# power_supply.net
KiCad netlist of a schematic drawn in Altium Designer
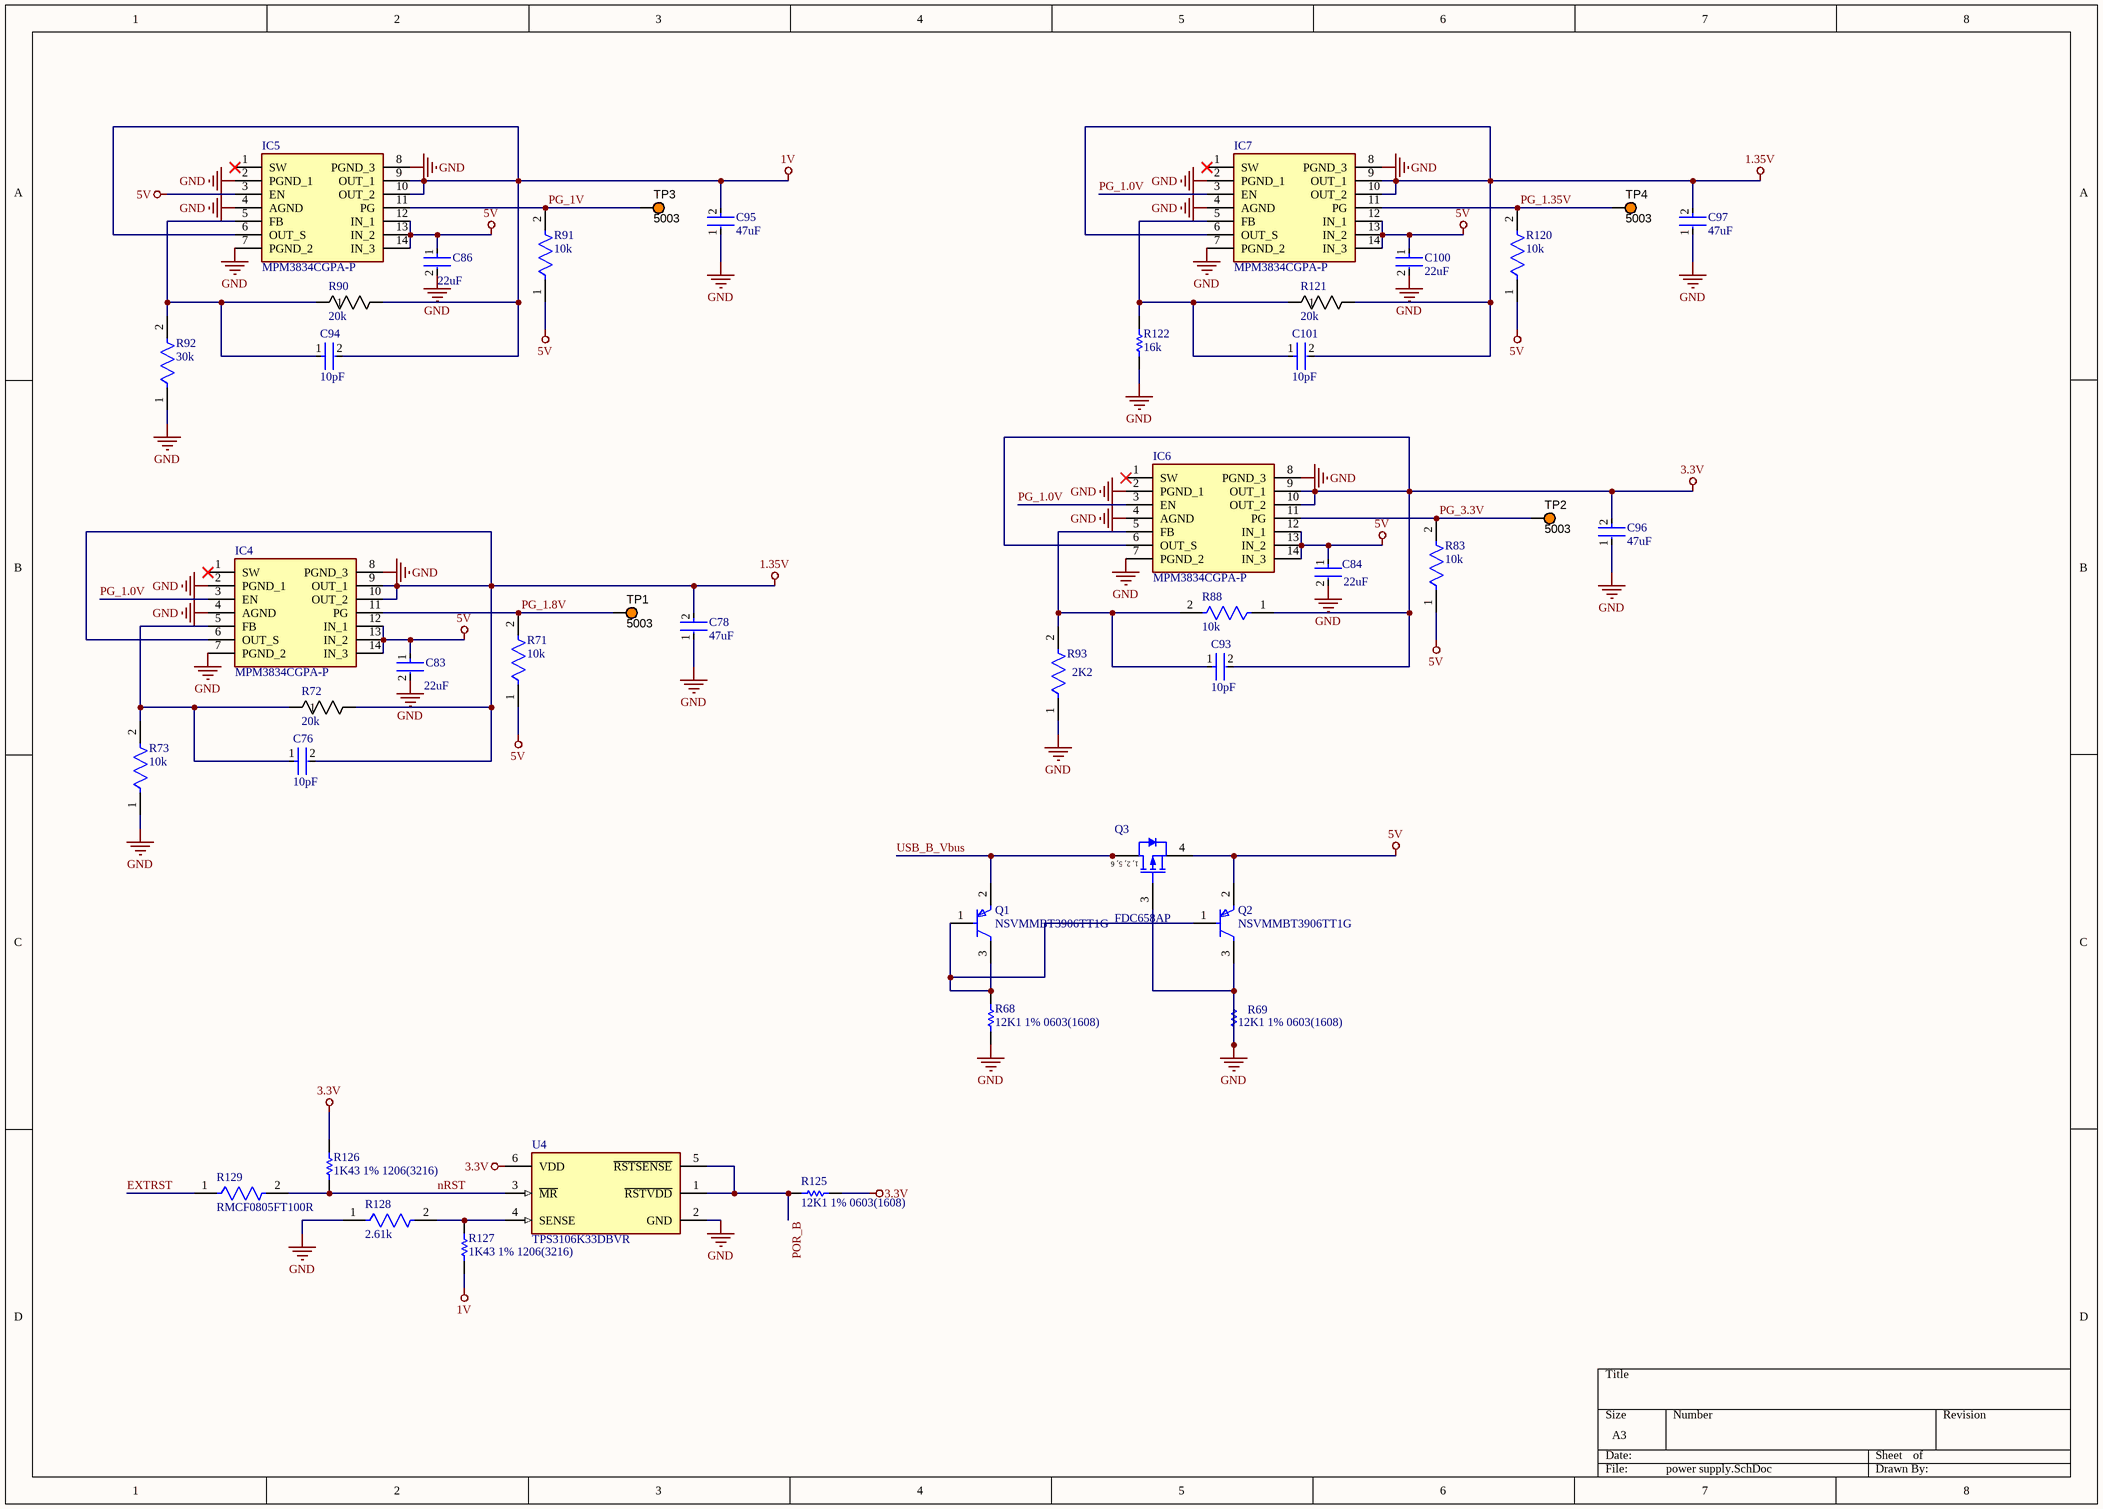
[diagram p0: power supply.SchDoc]

(export (version "E")
  (design (tool "Eeschema 10.0.6"))
  (components
    (comp (ref "C76")
      (value "10pF")
      (footprint "FP-0603-L_1_6_0_15-W_0_81-IPC_B")
      (description "General Purpose Ceramic Capacitor, 0603, 10pF, 2%, NP0, 30ppm/°C, 100V")
      (fields (field (name "TOLERANCE") "2%"))
      (libsource (lib "Altium Content Vault") (part "02cd4be3c70576c341d710602a673aa"))
    )
    (comp (ref "C78")
      (value "47uF")
      (footprint "FP-GRM31C-0_3-e0_3_0_8-IPC_C")
      (description "Chip Multilayer Ceramic Capacitors for General Purpose, 1206, 47uF, X5R, 15%, 20%, 16V")
      (fields (field (name "TOLERANCE") "20%"))
      (libsource (lib "Altium Content Vault") (part "f23184f103b6ebe33a8c269c53dcba6"))
    )
    (comp (ref "C83")
      (value "22uF")
      (footprint "FP-GRMJN7-0_1-IPC_C")
      (description "Chip Multilayer Ceramic Capacitors for General Purpose, 0704, 22uF, X5R, 15%, 20%, 16V")
      (libsource (lib "Altium Content Vault") (part "02cd4be3c70576c341d710602a673aa"))
    )
    (comp (ref "C84")
      (value "22uF")
      (footprint "FP-GRMJN7-0_1-IPC_C")
      (description "Chip Multilayer Ceramic Capacitors for General Purpose, 0704, 22uF, X5R, 15%, 20%, 16V")
      (libsource (lib "Altium Content Vault") (part "02cd4be3c70576c341d710602a673aa"))
    )
    (comp (ref "C86")
      (value "22uF")
      (footprint "FP-GRMJN7-0_1-IPC_C")
      (description "Chip Multilayer Ceramic Capacitors for General Purpose, 0704, 22uF, X5R, 15%, 20%, 16V")
      (libsource (lib "Altium Content Vault") (part "02cd4be3c70576c341d710602a673aa"))
    )
    (comp (ref "C93")
      (value "10pF")
      (footprint "FP-0603-L_1_6_0_15-W_0_81-IPC_B")
      (description "General Purpose Ceramic Capacitor, 0603, 10pF, 2%, NP0, 30ppm/°C, 100V")
      (fields (field (name "TOLERANCE") "2%"))
      (libsource (lib "Altium Content Vault") (part "02cd4be3c70576c341d710602a673aa"))
    )
    (comp (ref "C94")
      (value "10pF")
      (footprint "FP-0603-L_1_6_0_15-W_0_81-IPC_B")
      (description "General Purpose Ceramic Capacitor, 0603, 10pF, 2%, NP0, 30ppm/°C, 100V")
      (fields (field (name "TOLERANCE") "2%"))
      (libsource (lib "Altium Content Vault") (part "02cd4be3c70576c341d710602a673aa"))
    )
    (comp (ref "C95")
      (value "47uF")
      (footprint "FP-GRM31C-0_3-e0_3_0_8-IPC_C")
      (description "Chip Multilayer Ceramic Capacitors for General Purpose, 1206, 47uF, X5R, 15%, 20%, 16V")
      (fields (field (name "TOLERANCE") "20%"))
      (libsource (lib "Altium Content Vault") (part "f23184f103b6ebe33a8c269c53dcba6"))
    )
    (comp (ref "C96")
      (value "47uF")
      (footprint "FP-GRM31C-0_3-e0_3_0_8-IPC_C")
      (description "Chip Multilayer Ceramic Capacitors for General Purpose, 1206, 47uF, X5R, 15%, 20%, 16V")
      (fields (field (name "TOLERANCE") "20%"))
      (libsource (lib "Altium Content Vault") (part "f23184f103b6ebe33a8c269c53dcba6"))
    )
    (comp (ref "C97")
      (value "47uF")
      (footprint "FP-GRM31C-0_3-e0_3_0_8-IPC_C")
      (description "Chip Multilayer Ceramic Capacitors for General Purpose, 1206, 47uF, X5R, 15%, 20%, 16V")
      (fields (field (name "TOLERANCE") "20%"))
      (libsource (lib "Altium Content Vault") (part "f23184f103b6ebe33a8c269c53dcba6"))
    )
    (comp (ref "C100")
      (value "22uF")
      (footprint "FP-GRMJN7-0_1-IPC_C")
      (description "Chip Multilayer Ceramic Capacitors for General Purpose, 0704, 22uF, X5R, 15%, 20%, 16V")
      (libsource (lib "Altium Content Vault") (part "02cd4be3c70576c341d710602a673aa"))
    )
    (comp (ref "C101")
      (value "10pF")
      (footprint "FP-0603-L_1_6_0_15-W_0_81-IPC_B")
      (description "General Purpose Ceramic Capacitor, 0603, 10pF, 2%, NP0, 30ppm/°C, 100V")
      (fields (field (name "TOLERANCE") "2%"))
      (libsource (lib "Altium Content Vault") (part "02cd4be3c70576c341d710602a673aa"))
    )
    (comp (ref "IC4")
      (value "MPM3834CGPA-P")
      (footprint "SamacSys:MPM3834CGPAP")
      (description "Integrated Circuit")
      (fields (field (name "MOUSER PART NUMBER") "946-MPM3834CGPA-P"))
      (libsource (lib "*") (part "MPM3834CGPA-P"))
    )
    (comp (ref "IC5")
      (value "MPM3834CGPA-P")
      (footprint "SamacSys:MPM3834CGPAP")
      (description "Integrated Circuit")
      (fields (field (name "MOUSER PART NUMBER") "946-MPM3834CGPA-P"))
      (libsource (lib "*") (part "MPM3834CGPA-P"))
    )
    (comp (ref "IC6")
      (value "MPM3834CGPA-P")
      (footprint "SamacSys:MPM3834CGPAP")
      (description "Integrated Circuit")
      (fields (field (name "MOUSER PART NUMBER") "946-MPM3834CGPA-P"))
      (libsource (lib "*") (part "MPM3834CGPA-P"))
    )
    (comp (ref "IC7")
      (value "MPM3834CGPA-P")
      (footprint "SamacSys:MPM3834CGPAP")
      (description "Integrated Circuit")
      (fields (field (name "MOUSER PART NUMBER") "946-MPM3834CGPA-P"))
      (libsource (lib "*") (part "MPM3834CGPA-P"))
    )
    (comp (ref "Q1")
      (value "NSVMMBT3906TT1G")
      (footprint "FP-463-01-MFG")
      (description "NSVMMBT3906TT1G Small Signal Bipolar Transistor, 0.2A I(C), 40V V(BR)CEO, 1-Element, PNP, Silicon")
      (libsource (lib "Altium Content Vault") (part "ffd30bc5d0a750d7d7ef0ebafdf4ab0"))
    )
    (comp (ref "Q2")
      (value "NSVMMBT3906TT1G")
      (footprint "FP-463-01-MFG")
      (description "NSVMMBT3906TT1G Small Signal Bipolar Transistor, 0.2A I(C), 40V V(BR)CEO, 1-Element, PNP, Silicon")
      (libsource (lib "Altium Content Vault") (part "ffd30bc5d0a750d7d7ef0ebafdf4ab0"))
    )
    (comp (ref "Q3")
      (value "FDC658AP")
      (footprint "FAIR-SOT23-6_V")
      (fields (field (name "MANUFACTURER") "Fairchild Semiconductor"))
      (libsource (lib "Altium Content Vault") (part "PEMOS-DDGSDD-6"))
    )
    (comp (ref "R68")
      (value "12K1 1% 0603(1608)")
      (footprint "RESC0603(1608)_M")
      (description "12K1 0.1W 1% 0603 (1608 Metric)  SMD")
      (fields (field (name "POWER") "0.1 W") (field (name "TOLERANCE") "1 %"))
      (libsource (lib "Altium Content Vault") (part "RES"))
    )
    (comp (ref "R69")
      (value "12K1 1% 0603(1608)")
      (footprint "RESC0603(1608)_M")
      (description "12K1 0.1W 1% 0603 (1608 Metric)  SMD")
      (fields (field (name "POWER") "0.1 W") (field (name "TOLERANCE") "1 %"))
      (libsource (lib "Altium Content Vault") (part "RES"))
    )
    (comp (ref "R71")
      (value "10k")
      (footprint "FP-RN73R2A-IPC_A")
      (description "RES 10K OHM 0.1% 1/8W 0805")
      (libsource (lib "Altium Content Vault") (part "1029c3af85768c4190bb7ad29bc67b5"))
    )
    (comp (ref "R72")
      (value "20k")
      (footprint "RES_RCC0402_VIS")
      (description "RCC040220K0FKED Res Thick Film 0402 20K Ohm 1% 0.125W(1/8W) ±100ppm/°C Pad SMD Automotive T/R")
      (libsource (lib "Altium Content Vault") (part "RCC040220K0FKED"))
    )
    (comp (ref "R73")
      (value "10k")
      (footprint "FP-RN73R2A-IPC_A")
      (description "RES 10K OHM 0.1% 1/8W 0805")
      (libsource (lib "Altium Content Vault") (part "1029c3af85768c4190bb7ad29bc67b5"))
    )
    (comp (ref "R83")
      (value "10k")
      (footprint "FP-RN73R2A-IPC_A")
      (description "RES 10K OHM 0.1% 1/8W 0805")
      (libsource (lib "Altium Content Vault") (part "1029c3af85768c4190bb7ad29bc67b5"))
    )
    (comp (ref "R88")
      (value "10k")
      (footprint "FP-RN73R2A-IPC_A")
      (description "RES 10K OHM 0.1% 1/8W 0805")
      (libsource (lib "Altium Content Vault") (part "1029c3af85768c4190bb7ad29bc67b5"))
    )
    (comp (ref "R90")
      (value "20k")
      (footprint "RES_RCC0402_VIS")
      (description "RCC040220K0FKED Res Thick Film 0402 20K Ohm 1% 0.125W(1/8W) ±100ppm/°C Pad SMD Automotive T/R")
      (libsource (lib "Altium Content Vault") (part "RCC040220K0FKED"))
    )
    (comp (ref "R91")
      (value "10k")
      (footprint "FP-RN73R2A-IPC_A")
      (description "RES 10K OHM 0.1% 1/8W 0805")
      (libsource (lib "Altium Content Vault") (part "1029c3af85768c4190bb7ad29bc67b5"))
    )
    (comp (ref "R92")
      (value "30k")
      (footprint "FP-RMCF0603-IPC_A")
      (description "30kΩ ±5% 0.1W 0603 Thick Film Chip Resistor AEC-Q200 compliant")
      (fields (field (name "TOLERANCE") "5%"))
      (libsource (lib "Altium Content Vault") (part "1029c3af85768c4190bb7ad29bc67b5"))
    )
    (comp (ref "R93")
      (value "2K2")
      (footprint "FP-LTR10-IPC_B")
      (description "High power chip resistors wide terminal type 2.2kΩ 5% 0.25W 0508")
      (fields (field (name "TOLERANCE") "5%"))
      (libsource (lib "Altium Content Vault") (part "1029c3af85768c4190bb7ad29bc67b5"))
    )
    (comp (ref "R120")
      (value "10k")
      (footprint "FP-RN73R2A-IPC_A")
      (description "RES 10K OHM 0.1% 1/8W 0805")
      (libsource (lib "Altium Content Vault") (part "1029c3af85768c4190bb7ad29bc67b5"))
    )
    (comp (ref "R121")
      (value "20k")
      (footprint "RES_RCC0402_VIS")
      (description "RCC040220K0FKED Res Thick Film 0402 20K Ohm 1% 0.125W(1/8W) ±100ppm/°C Pad SMD Automotive T/R")
      (libsource (lib "Altium Content Vault") (part "RCC040220K0FKED"))
    )
    (comp (ref "R122")
      (value "16k")
      (footprint "RESC0603X28X15LL05T05")
      (fields (field (name "PART NUMBER") "CRCW020116K0JNED") (field (name "MANUFACTURER") "Vishay Dale"))
      (libsource (lib "Altium Content Vault") (part "RES"))
    )
    (comp (ref "R125")
      (value "12K1 1% 0603(1608)")
      (footprint "RESC0603(1608)_M")
      (description "12K1 0.1W 1% 0603 (1608 Metric)  SMD")
      (fields (field (name "POWER") "0.1 W") (field (name "TOLERANCE") "1 %"))
      (libsource (lib "Altium Content Vault") (part "RES"))
    )
    (comp (ref "R126")
      (value "1K43 1% 1206(3216)")
      (footprint "RESC1206(3216)_M")
      (description "1K43 0.25W 1% 1206 (3216 Metric)  SMD")
      (fields (field (name "POWER") "0.25 W") (field (name "TOLERANCE") "1 %"))
      (libsource (lib "Altium Content Vault") (part "RES"))
    )
    (comp (ref "R127")
      (value "1K43 1% 1206(3216)")
      (footprint "RESC1206(3216)_M")
      (description "1K43 0.25W 1% 1206 (3216 Metric)  SMD")
      (fields (field (name "POWER") "0.25 W") (field (name "TOLERANCE") "1 %"))
      (libsource (lib "Altium Content Vault") (part "RES"))
    )
    (comp (ref "R128")
      (value "2.61k")
      (footprint "FP-RK73H1J-IPC_B")
      (description "2.61kΩ ±0.5% 0.1W Chip Resistor 0603 Thick Film AEC-Q200 Qualified")
      (libsource (lib "Altium Content Vault") (part "1029c3af85768c4190bb7ad29bc67b5"))
    )
    (comp (ref "R129")
      (value "RMCF0805FT100R")
      (footprint "FP-RMCF0805-IPC_A")
      (description "100Ω ±1% 0.125W 0805 Thick Film Chip Resistor AEC-Q200 compliant")
      (fields (field (name "TOLERANCE") "1%"))
      (libsource (lib "Altium Content Vault") (part "1029c3af85768c4190bb7ad29bc67b5"))
    )
    (comp (ref "TP1")
      (value "5003")
      (footprint "KSTN-5003")
      (description "Test Point, Orange, 1-Pin THD, RoHS")
      (libsource (lib "Altium Content Vault") (part "TESTPOINT_ORANGE"))
    )
    (comp (ref "TP2")
      (value "5003")
      (footprint "KSTN-5003")
      (description "Test Point, Orange, 1-Pin THD, RoHS")
      (libsource (lib "Altium Content Vault") (part "TESTPOINT_ORANGE"))
    )
    (comp (ref "TP3")
      (value "5003")
      (footprint "KSTN-5003")
      (description "Test Point, Orange, 1-Pin THD, RoHS")
      (libsource (lib "Altium Content Vault") (part "TESTPOINT_ORANGE"))
    )
    (comp (ref "TP4")
      (value "5003")
      (footprint "KSTN-5003")
      (description "Test Point, Orange, 1-Pin THD, RoHS")
      (libsource (lib "Altium Content Vault") (part "TESTPOINT_ORANGE"))
    )
    (comp (ref "U4")
      (value "TPS3106K33DBVR")
      (footprint "FP-DBV0006A-MFG")
      (description "IC SUPERVISORY CIRCUIT SOT-23-6")
      (fields
        (field (name "OCTOPART") "https://octopart.com/tps3106k33dbvr-texas+instruments-505820")
        (field (name "MANUFACTURER") "Texas Instruments")
      )
      (libsource (lib "Altium Content Vault") (part "1e400620819f6d8b17379bded79418f"))
    )
  )
  (nets
    (net (code "1") (name "/ PG_1.8V") (class "Default")
      (node (ref "IC4") (pin "11") (pinfunction "PG_11") (pintype "passive"))
      (node (ref "R71") (pin "2") (pinfunction "2_2") (pintype "passive"))
      (node (ref "TP1") (pin "1") (pinfunction "1_1") (pintype "passive"))
    )
    (net (code "2") (name "/ PG_1.35V") (class "Default")
      (node (ref "IC7") (pin "11") (pinfunction "PG_11") (pintype "passive"))
      (node (ref "R120") (pin "2") (pinfunction "2_2") (pintype "passive"))
      (node (ref "TP4") (pin "1") (pinfunction "1_1") (pintype "passive"))
    )
    (net (code "3") (name "/ PG_1V") (class "Default")
      (node (ref "IC5") (pin "11") (pinfunction "PG_11") (pintype "passive"))
      (node (ref "R91") (pin "2") (pinfunction "2_2") (pintype "passive"))
      (node (ref "TP3") (pin "1") (pinfunction "1_1") (pintype "passive"))
    )
    (net (code "4") (name "/ PG_3.3V") (class "Default")
      (node (ref "IC6") (pin "11") (pinfunction "PG_11") (pintype "passive"))
      (node (ref "R83") (pin "2") (pinfunction "2_2") (pintype "passive"))
      (node (ref "TP2") (pin "1") (pinfunction "1_1") (pintype "passive"))
    )
    (net (code "5") (name "/EXTRST") (class "Default")
      (node (ref "R129") (pin "1") (pinfunction "1_1") (pintype "passive"))
    )
    (net (code "6") (name "/PG_1.0V") (class "Default")
      (node (ref "IC4") (pin "3") (pinfunction "EN_3") (pintype "passive"))
      (node (ref "IC6") (pin "3") (pinfunction "EN_3") (pintype "passive"))
      (node (ref "IC7") (pin "3") (pinfunction "EN_3") (pintype "passive"))
    )
    (net (code "7") (name "/POR_B") (class "Default")
      (node (ref "R125") (pin "2") (pinfunction "2_2") (pintype "passive"))
      (node (ref "U4") (pin "1") (pinfunction "~{RSTVDD}_1") (pintype "open_collector"))
      (node (ref "U4") (pin "5") (pinfunction "~{RSTSENSE}_5") (pintype "open_collector"))
    )
    (net (code "8") (name "/USB_B_Vbus") (class "Default")
      (node (ref "Q1") (pin "2") (pinfunction "E_2") (pintype "passive"))
      (node (ref "Q3") (pin "1") (pinfunction "DRAIN_1") (pintype "passive"))
      (node (ref "Q3") (pin "2") (pinfunction "DRAIN_2") (pintype "passive"))
      (node (ref "Q3") (pin "5") (pinfunction "DRAIN_5") (pintype "passive"))
      (node (ref "Q3") (pin "6") (pinfunction "DRAIN_6") (pintype "passive"))
    )
    (net (code "9") (name "/nRST") (class "Default")
      (node (ref "R126") (pin "1") (pinfunction "1_1") (pintype "passive"))
      (node (ref "R129") (pin "2") (pinfunction "2_2") (pintype "passive"))
      (node (ref "U4") (pin "3") (pinfunction "~{MR}_3") (pintype "input"))
    )
    (net (code "10") (name "1.35V") (class "Default")
      (node (ref "C101") (pin "2") (pinfunction "2_2") (pintype "passive"))
      (node (ref "C76") (pin "2") (pinfunction "2_2") (pintype "passive"))
      (node (ref "C78") (pin "2") (pinfunction "2_2") (pintype "passive"))
      (node (ref "C97") (pin "2") (pinfunction "2_2") (pintype "passive"))
      (node (ref "IC4") (pin "10") (pinfunction "OUT_2_10") (pintype "passive"))
      (node (ref "IC4") (pin "6") (pinfunction "OUT_S_6") (pintype "passive"))
      (node (ref "IC4") (pin "9") (pinfunction "OUT_1_9") (pintype "passive"))
      (node (ref "IC7") (pin "10") (pinfunction "OUT_2_10") (pintype "passive"))
      (node (ref "IC7") (pin "6") (pinfunction "OUT_S_6") (pintype "passive"))
      (node (ref "IC7") (pin "9") (pinfunction "OUT_1_9") (pintype "passive"))
      (node (ref "R121") (pin "2") (pinfunction "2_2") (pintype "passive"))
      (node (ref "R72") (pin "2") (pinfunction "2_2") (pintype "passive"))
    )
    (net (code "11") (name "1V") (class "Default")
      (node (ref "C94") (pin "2") (pinfunction "2_2") (pintype "passive"))
      (node (ref "C95") (pin "2") (pinfunction "2_2") (pintype "passive"))
      (node (ref "IC5") (pin "10") (pinfunction "OUT_2_10") (pintype "passive"))
      (node (ref "IC5") (pin "6") (pinfunction "OUT_S_6") (pintype "passive"))
      (node (ref "IC5") (pin "9") (pinfunction "OUT_1_9") (pintype "passive"))
      (node (ref "R127") (pin "1") (pinfunction "1_1") (pintype "passive"))
      (node (ref "R90") (pin "2") (pinfunction "2_2") (pintype "passive"))
    )
    (net (code "12") (name "3.3V") (class "Default")
      (node (ref "C93") (pin "2") (pinfunction "2_2") (pintype "passive"))
      (node (ref "C96") (pin "2") (pinfunction "2_2") (pintype "passive"))
      (node (ref "IC6") (pin "10") (pinfunction "OUT_2_10") (pintype "passive"))
      (node (ref "IC6") (pin "6") (pinfunction "OUT_S_6") (pintype "passive"))
      (node (ref "IC6") (pin "9") (pinfunction "OUT_1_9") (pintype "passive"))
      (node (ref "R125") (pin "1") (pinfunction "1_1") (pintype "passive"))
      (node (ref "R126") (pin "2") (pinfunction "2_2") (pintype "passive"))
      (node (ref "R88") (pin "1") (pinfunction "1_1") (pintype "passive"))
      (node (ref "U4") (pin "6") (pinfunction "VDD_6") (pintype "power_in"))
    )
    (net (code "13") (name "5V") (class "Default")
      (node (ref "C100") (pin "1") (pinfunction "1_1") (pintype "passive"))
      (node (ref "C83") (pin "1") (pinfunction "1_1") (pintype "passive"))
      (node (ref "C84") (pin "1") (pinfunction "1_1") (pintype "passive"))
      (node (ref "C86") (pin "1") (pinfunction "1_1") (pintype "passive"))
      (node (ref "IC4") (pin "12") (pinfunction "IN_1_12") (pintype "passive"))
      (node (ref "IC4") (pin "13") (pinfunction "IN_2_13") (pintype "passive"))
      (node (ref "IC4") (pin "14") (pinfunction "IN_3_14") (pintype "passive"))
      (node (ref "IC5") (pin "12") (pinfunction "IN_1_12") (pintype "passive"))
      (node (ref "IC5") (pin "13") (pinfunction "IN_2_13") (pintype "passive"))
      (node (ref "IC5") (pin "14") (pinfunction "IN_3_14") (pintype "passive"))
      (node (ref "IC5") (pin "3") (pinfunction "EN_3") (pintype "passive"))
      (node (ref "IC6") (pin "12") (pinfunction "IN_1_12") (pintype "passive"))
      (node (ref "IC6") (pin "13") (pinfunction "IN_2_13") (pintype "passive"))
      (node (ref "IC6") (pin "14") (pinfunction "IN_3_14") (pintype "passive"))
      (node (ref "IC7") (pin "12") (pinfunction "IN_1_12") (pintype "passive"))
      (node (ref "IC7") (pin "13") (pinfunction "IN_2_13") (pintype "passive"))
      (node (ref "IC7") (pin "14") (pinfunction "IN_3_14") (pintype "passive"))
      (node (ref "Q2") (pin "2") (pinfunction "E_2") (pintype "passive"))
      (node (ref "Q3") (pin "4") (pinfunction "SOURCE_4") (pintype "passive"))
      (node (ref "R120") (pin "1") (pinfunction "1_1") (pintype "passive"))
      (node (ref "R71") (pin "1") (pinfunction "1_1") (pintype "passive"))
      (node (ref "R83") (pin "1") (pinfunction "1_1") (pintype "passive"))
      (node (ref "R91") (pin "1") (pinfunction "1_1") (pintype "passive"))
    )
    (net (code "14") (name "GND") (class "Default")
      (node (ref "C100") (pin "2") (pinfunction "2_2") (pintype "passive"))
      (node (ref "C78") (pin "1") (pinfunction "1_1") (pintype "passive"))
      (node (ref "C83") (pin "2") (pinfunction "2_2") (pintype "passive"))
      (node (ref "C84") (pin "2") (pinfunction "2_2") (pintype "passive"))
      (node (ref "C86") (pin "2") (pinfunction "2_2") (pintype "passive"))
      (node (ref "C95") (pin "1") (pinfunction "1_1") (pintype "passive"))
      (node (ref "C96") (pin "1") (pinfunction "1_1") (pintype "passive"))
      (node (ref "C97") (pin "1") (pinfunction "1_1") (pintype "passive"))
      (node (ref "IC4") (pin "2") (pinfunction "PGND_1_2") (pintype "passive"))
      (node (ref "IC4") (pin "4") (pinfunction "AGND_4") (pintype "passive"))
      (node (ref "IC4") (pin "7") (pinfunction "PGND_2_7") (pintype "passive"))
      (node (ref "IC4") (pin "8") (pinfunction "PGND_3_8") (pintype "passive"))
      (node (ref "IC5") (pin "2") (pinfunction "PGND_1_2") (pintype "passive"))
      (node (ref "IC5") (pin "4") (pinfunction "AGND_4") (pintype "passive"))
      (node (ref "IC5") (pin "7") (pinfunction "PGND_2_7") (pintype "passive"))
      (node (ref "IC5") (pin "8") (pinfunction "PGND_3_8") (pintype "passive"))
      (node (ref "IC6") (pin "2") (pinfunction "PGND_1_2") (pintype "passive"))
      (node (ref "IC6") (pin "4") (pinfunction "AGND_4") (pintype "passive"))
      (node (ref "IC6") (pin "7") (pinfunction "PGND_2_7") (pintype "passive"))
      (node (ref "IC6") (pin "8") (pinfunction "PGND_3_8") (pintype "passive"))
      (node (ref "IC7") (pin "2") (pinfunction "PGND_1_2") (pintype "passive"))
      (node (ref "IC7") (pin "4") (pinfunction "AGND_4") (pintype "passive"))
      (node (ref "IC7") (pin "7") (pinfunction "PGND_2_7") (pintype "passive"))
      (node (ref "IC7") (pin "8") (pinfunction "PGND_3_8") (pintype "passive"))
      (node (ref "Q2") (pin "3") (pinfunction "C_3") (pintype "passive"))
      (node (ref "Q3") (pin "3") (pinfunction "GATE_3") (pintype "passive"))
      (node (ref "R122") (pin "1") (pinfunction "1_1") (pintype "passive"))
      (node (ref "R128") (pin "1") (pinfunction "1_1") (pintype "passive"))
      (node (ref "R68") (pin "1") (pinfunction "1_1") (pintype "passive"))
      (node (ref "R69") (pin "1") (pinfunction "1_1") (pintype "passive"))
      (node (ref "R69") (pin "2") (pinfunction "2_2") (pintype "passive"))
      (node (ref "R73") (pin "1") (pinfunction "1_1") (pintype "passive"))
      (node (ref "R92") (pin "1") (pinfunction "1_1") (pintype "passive"))
      (node (ref "R93") (pin "1") (pinfunction "1_1") (pintype "passive"))
      (node (ref "U4") (pin "2") (pinfunction "GND_2") (pintype "power_in"))
    )
    (net (code "15") (name "Net-(IC4-FB)") (class "Default")
      (node (ref "C76") (pin "1") (pinfunction "1_1") (pintype "passive"))
      (node (ref "IC4") (pin "5") (pinfunction "FB_5") (pintype "passive"))
      (node (ref "R72") (pin "1") (pinfunction "1_1") (pintype "passive"))
      (node (ref "R73") (pin "2") (pinfunction "2_2") (pintype "passive"))
    )
    (net (code "16") (name "Net-(IC5-FB)") (class "Default")
      (node (ref "C94") (pin "1") (pinfunction "1_1") (pintype "passive"))
      (node (ref "IC5") (pin "5") (pinfunction "FB_5") (pintype "passive"))
      (node (ref "R90") (pin "1") (pinfunction "1_1") (pintype "passive"))
      (node (ref "R92") (pin "2") (pinfunction "2_2") (pintype "passive"))
    )
    (net (code "17") (name "Net-(IC6-FB)") (class "Default")
      (node (ref "C93") (pin "1") (pinfunction "1_1") (pintype "passive"))
      (node (ref "IC6") (pin "5") (pinfunction "FB_5") (pintype "passive"))
      (node (ref "R88") (pin "2") (pinfunction "2_2") (pintype "passive"))
      (node (ref "R93") (pin "2") (pinfunction "2_2") (pintype "passive"))
    )
    (net (code "18") (name "Net-(IC7-FB)") (class "Default")
      (node (ref "C101") (pin "1") (pinfunction "1_1") (pintype "passive"))
      (node (ref "IC7") (pin "5") (pinfunction "FB_5") (pintype "passive"))
      (node (ref "R121") (pin "1") (pinfunction "1_1") (pintype "passive"))
      (node (ref "R122") (pin "2") (pinfunction "2_2") (pintype "passive"))
    )
    (net (code "19") (name "Net-(Q1-B)") (class "Default")
      (node (ref "Q1") (pin "1") (pinfunction "B_1") (pintype "passive"))
      (node (ref "Q1") (pin "3") (pinfunction "C_3") (pintype "passive"))
      (node (ref "Q2") (pin "1") (pinfunction "B_1") (pintype "passive"))
      (node (ref "R68") (pin "2") (pinfunction "2_2") (pintype "passive"))
    )
    (net (code "20") (name "Net-(U4-SENSE)") (class "Default")
      (node (ref "R127") (pin "2") (pinfunction "2_2") (pintype "passive"))
      (node (ref "R128") (pin "2") (pinfunction "2_2") (pintype "passive"))
      (node (ref "U4") (pin "4") (pinfunction "SENSE_4") (pintype "input"))
    )
    (net (code "21") (name "unconnected-(IC4-SW-Pad1)") (class "Default")
      (node (ref "IC4") (pin "1") (pinfunction "SW_1") (pintype "passive+no_connect"))
    )
    (net (code "22") (name "unconnected-(IC5-SW-Pad1)") (class "Default")
      (node (ref "IC5") (pin "1") (pinfunction "SW_1") (pintype "passive+no_connect"))
    )
    (net (code "23") (name "unconnected-(IC6-SW-Pad1)") (class "Default")
      (node (ref "IC6") (pin "1") (pinfunction "SW_1") (pintype "passive+no_connect"))
    )
    (net (code "24") (name "unconnected-(IC7-SW-Pad1)") (class "Default")
      (node (ref "IC7") (pin "1") (pinfunction "SW_1") (pintype "passive+no_connect"))
    )
  )
)
